# Power_-_1V2.net
KiCad netlist of a schematic drawn in Altium Designer
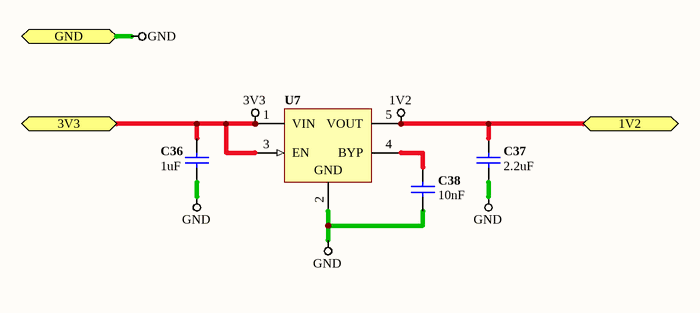
[diagram p0: Power - 1V2.SchDoc]

(export (version "E")
  (design (tool "Eeschema 10.0.6"))
  (components
    (comp (ref "C36")
      (value "1uF")
      (footprint "CAPC0402(1005)60_L")
      (description "CAP 1uF 16V ±10% 0402 (1005 Metric) Thickness 0.6mm SMD")
      (fields
        (field (name "TOLERANCE") "±10%")
        (field (name "MANUFACTURER PART NUMBER") "C1005X5R1C105K050BC")
      )
      (libsource (lib "Altium Content Vault") (part "CMP-1034-02119-1"))
    )
    (comp (ref "C37")
      (value "2.2uF")
      (footprint "CAPC0603(1608)55_L")
      (description "CAP 2.2uF 16V ±10% 0603 (1608 Metric) Thickness 0.55mm SMD")
      (fields (field (name "TOLERANCE") "±10%") (field (name "MANUFACTURER PART NUMBER") "C0603C225K4PACTU"))
      (libsource (lib "Altium Content Vault") (part "CMP-1035-02762-1"))
    )
    (comp (ref "C38")
      (value "10nF")
      (footprint "CAPC0402(1005)33_L")
      (description "CAP 10nF 16V ±10% 0402 (1005 Metric) Thickness 0.33mm SMD")
      (fields
        (field (name "TOLERANCE") "±10%")
        (field (name "MANUFACTURER PART NUMBER") "GRM155R61C103KA01D")
      )
      (libsource (lib "Altium Content Vault") (part "CMP-1034-01875-1"))
    )
    (comp (ref "U7")
      (value "CAT6219-125TDGT3")
      (footprint "ONSC-SOT23-5_M")
      (description "Fixed Low Drop Positive Voltage Regulator, 1.2V 5-Pin TSOT-23, Tape and Reel")
      (fields (field (name "PARTNUMBER") "CAT6219-330TDGT3") (field (name "MANUFACTURER") "ON Semiconductor"))
      (libsource (lib "CAT6219-125TDGT3") (part "CAT6219-125TDGT3"))
    )
  )
  (nets
    (net (code "1") (name "1V2") (class "Default")
      (node (ref "C37") (pin "2") (pinfunction "2_2") (pintype "passive"))
      (node (ref "U7") (pin "5") (pinfunction "VOUT_5") (pintype "power_in"))
    )
    (net (code "2") (name "3V3") (class "Default")
      (node (ref "C36") (pin "2") (pinfunction "2_2") (pintype "passive"))
      (node (ref "U7") (pin "1") (pinfunction "VIN_1") (pintype "power_in"))
      (node (ref "U7") (pin "3") (pinfunction "EN_3") (pintype "input"))
    )
    (net (code "3") (name "GND") (class "Default")
      (node (ref "C36") (pin "1") (pinfunction "1_1") (pintype "passive"))
      (node (ref "C37") (pin "1") (pinfunction "1_1") (pintype "passive"))
      (node (ref "C38") (pin "1") (pinfunction "1_1") (pintype "passive"))
      (node (ref "U7") (pin "2") (pinfunction "GND_2") (pintype "power_in"))
    )
    (net (code "4") (name "Net-(U7-BYP)") (class "Default")
      (node (ref "C38") (pin "2") (pinfunction "2_2") (pintype "passive"))
      (node (ref "U7") (pin "4") (pinfunction "BYP_4") (pintype "passive"))
    )
  )
)
